# ProPrj_Line_Follower_TURBO_v1_2_2026-04-.net
KiCad netlist of a schematic drawn in EasyEDA Pro
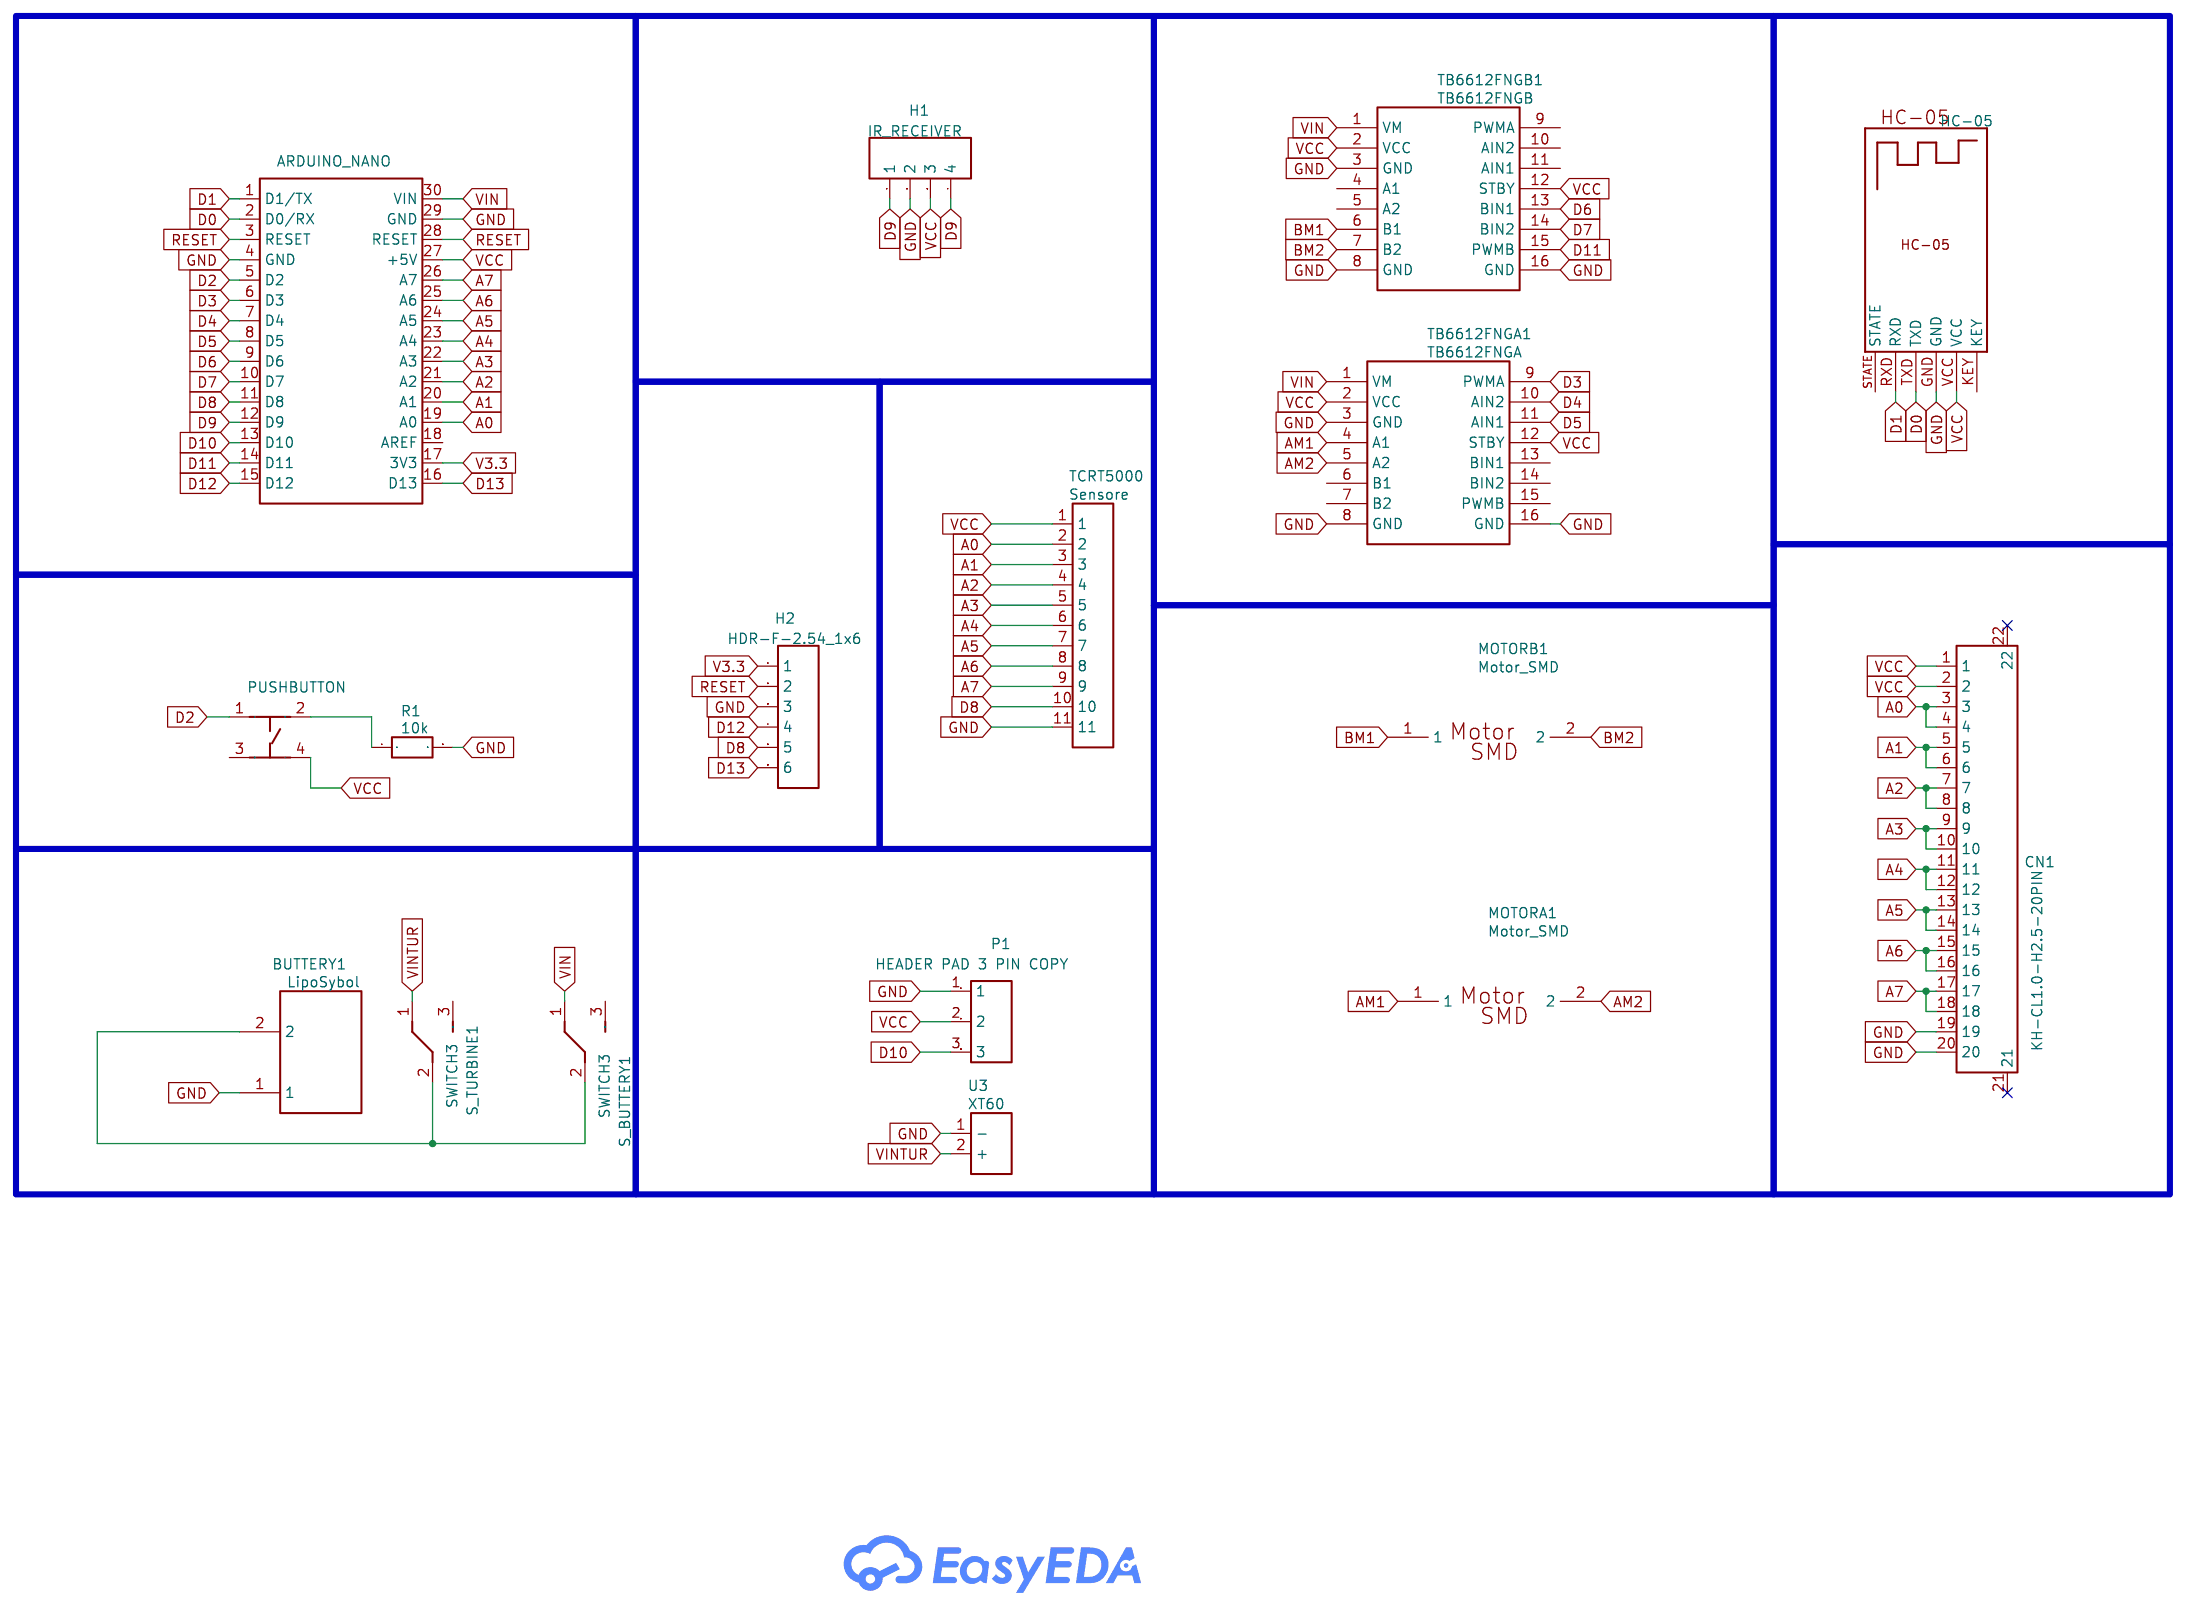
[diagram p0: schematic sheet]

(export (version "E")
  (design (tool "Eeschema 10.0.6"))
  (components
    (comp (ref "1")
      (value "HC-05")
      (footprint "easyedapro:HC-05")
      (fields (field (name "Contributor") "cingoz57"))
      (libsource (lib "easyedapro") (part "HC-05"))
    )
    (comp (ref "ARDUINO_NANO1")
      (value "ARDUINO_NANO")
      (footprint "easyedapro:COMM-TH_ARDUINO_NANO")
      (fields (field (name "Contributor") "lcsc"))
      (libsource (lib "easyedapro") (part "ARDUINO_NANO"))
    )
    (comp (ref "BUTTERY1")
      (value "LipoSybol")
      (footprint "easyedapro:2PIN-RMC")
      (fields (field (name "Contributor") "tech1service"))
      (libsource (lib "easyedapro") (part "LipoSybol"))
    )
    (comp (ref "CN1")
      (value "KH-CL1.0-H2.5-20PIN")
      (footprint "easyedapro:FPC-SMD_KH-CL1.0-H2.5-20PIN")
      (fields (field (name "Manufacturer") "kinghelm(金航标)") (field (name "Contributor") "LCSC"))
      (libsource (lib "easyedapro") (part "KH-CL1.0-H2.5-20PIN"))
    )
    (comp (ref "D2")
      (value "PUSHBUTTON")
      (footprint "easyedapro:SW-SMD_4P-L6.0-W6.0-P4.50-LS10.0_TL3301EF160QG")
      (fields
        (field (name "Manufacturer Part") "4pinTACTPCBTHTPushButton")
        (field (name "Contributor") "LCSC")
      )
      (libsource (lib "easyedapro") (part "PUSHBUTTON"))
    )
    (comp (ref "H1")
      (value "IR_RECEIVER")
      (footprint "easyedapro:HDR-F-2.54_1X4")
      (fields (field (name "Contributor") "LCEDA_Lib"))
      (libsource (lib "easyedapro") (part "IR_RECEIVER"))
    )
    (comp (ref "H2")
      (value "HDR-F-2.54_1x6")
      (footprint "easyedapro:HDR-F-2.54_1X6")
      (fields (field (name "Contributor") "LCEDA_Lib"))
      (libsource (lib "easyedapro") (part "HDR-F-2.54_1x6"))
    )
    (comp (ref "MOTORA1")
      (value "Motor_SMD")
      (footprint "easyedapro:MOTORSMD")
      (fields (field (name "Manufacturer Part") "RayitoCorp") (field (name "Contributor") "Josueking23"))
      (libsource (lib "easyedapro") (part "Motor_SMD"))
    )
    (comp (ref "MOTORB1")
      (value "Motor_SMD")
      (footprint "easyedapro:MOTORSMD")
      (fields (field (name "Manufacturer Part") "RayitoCorp") (field (name "Contributor") "Josueking23"))
      (libsource (lib "easyedapro") (part "Motor_SMD"))
    )
    (comp (ref "P1")
      (value "HEADER PAD 3 PIN COPY")
      (footprint "easyedapro:CONNECTOR_PINHEADER_2.54MM:PINHEADER_1X3")
      (fields
        (field (name "Manufacturer Part") "Female headerHDR1X8-2.54")
        (field (name "Manufacturer") "BOOMELE")
        (field (name "Contributor") "juchani")
      )
      (libsource (lib "easyedapro") (part "HEADER PAD 3 PIN COPY"))
    )
    (comp (ref "R1")
      (value "10k")
      (footprint "easyedapro:R0603")
      (fields (field (name "Contributor") "LCEDA_Lib"))
      (libsource (lib "easyedapro") (part "10k"))
    )
    (comp (ref "S_BUTTERY1")
      (value "SWITCH3")
      (footprint "easyedapro:SWITCH3PINS-DIP")
      (fields (field (name "Contributor") "TruongKhoa"))
      (libsource (lib "easyedapro") (part "SWITCH3"))
    )
    (comp (ref "S_TURBINE1")
      (value "SWITCH3")
      (footprint "easyedapro:SWITCH3PINS-DIP")
      (fields (field (name "Contributor") "TruongKhoa"))
      (libsource (lib "easyedapro") (part "SWITCH3"))
    )
    (comp (ref "TB6612FNGA1")
      (value "TB6612FNGA")
      (footprint "easyedapro:TB6612FNG")
      (fields (field (name "Manufacturer Part") "TB6612FNG") (field (name "Contributor") "NonpawitE"))
      (libsource (lib "easyedapro") (part "TB6612FNGA"))
    )
    (comp (ref "TB6612FNGB1")
      (value "TB6612FNGB")
      (footprint "easyedapro:TB6612FNG")
      (fields (field (name "Manufacturer Part") "TB6612FNG") (field (name "Contributor") "NonpawitE"))
      (libsource (lib "easyedapro") (part "TB6612FNGB"))
    )
    (comp (ref "TCRT5000")
      (value "Sensore")
      (fields (field (name "Manufacturer Part") "HDR-1X11") (field (name "Contributor") "LCSC"))
      (libsource (lib "easyedapro") (part "Sensore"))
    )
    (comp (ref "U3")
      (value "XT60")
      (footprint "easyedapro:CONN-TH_XT60")
      (fields
        (field (name "Manufacturer Part") "XT60-M.")
        (field (name "Manufacturer") "AMASS(艾迈斯)")
        (field (name "Contributor") "lcsc")
      )
      (libsource (lib "easyedapro") (part "XT60"))
    )
  )
  (nets
    (net (code "1") (name "A0") (class "Default")
      (node (ref "ARDUINO_NANO1") (pin "19") (pinfunction "A0_19") (pintype "unspecified"))
      (node (ref "CN1") (pin "3") (pinfunction "3_3") (pintype "unspecified"))
      (node (ref "CN1") (pin "4") (pinfunction "4_4") (pintype "unspecified"))
      (node (ref "TCRT5000") (pin "2") (pinfunction "2_2") (pintype "unspecified"))
    )
    (net (code "2") (name "A1") (class "Default")
      (node (ref "ARDUINO_NANO1") (pin "20") (pinfunction "A1_20") (pintype "unspecified"))
      (node (ref "CN1") (pin "5") (pinfunction "5_5") (pintype "unspecified"))
      (node (ref "CN1") (pin "6") (pinfunction "6_6") (pintype "unspecified"))
      (node (ref "TCRT5000") (pin "3") (pinfunction "3_3") (pintype "unspecified"))
    )
    (net (code "3") (name "A2") (class "Default")
      (node (ref "ARDUINO_NANO1") (pin "21") (pinfunction "A2_21") (pintype "unspecified"))
      (node (ref "CN1") (pin "7") (pinfunction "7_7") (pintype "unspecified"))
      (node (ref "CN1") (pin "8") (pinfunction "8_8") (pintype "unspecified"))
      (node (ref "TCRT5000") (pin "4") (pinfunction "4_4") (pintype "unspecified"))
    )
    (net (code "4") (name "A3") (class "Default")
      (node (ref "ARDUINO_NANO1") (pin "22") (pinfunction "A3_22") (pintype "unspecified"))
      (node (ref "CN1") (pin "10") (pinfunction "10_10") (pintype "unspecified"))
      (node (ref "CN1") (pin "9") (pinfunction "9_9") (pintype "unspecified"))
      (node (ref "TCRT5000") (pin "5") (pinfunction "5_5") (pintype "unspecified"))
    )
    (net (code "5") (name "A4") (class "Default")
      (node (ref "ARDUINO_NANO1") (pin "23") (pinfunction "A4_23") (pintype "unspecified"))
      (node (ref "CN1") (pin "11") (pinfunction "11_11") (pintype "unspecified"))
      (node (ref "CN1") (pin "12") (pinfunction "12_12") (pintype "unspecified"))
      (node (ref "TCRT5000") (pin "6") (pinfunction "6_6") (pintype "unspecified"))
    )
    (net (code "6") (name "A5") (class "Default")
      (node (ref "ARDUINO_NANO1") (pin "24") (pinfunction "A5_24") (pintype "unspecified"))
      (node (ref "CN1") (pin "13") (pinfunction "13_13") (pintype "unspecified"))
      (node (ref "CN1") (pin "14") (pinfunction "14_14") (pintype "unspecified"))
      (node (ref "TCRT5000") (pin "7") (pinfunction "7_7") (pintype "unspecified"))
    )
    (net (code "7") (name "A6") (class "Default")
      (node (ref "ARDUINO_NANO1") (pin "25") (pinfunction "A6_25") (pintype "unspecified"))
      (node (ref "CN1") (pin "15") (pinfunction "15_15") (pintype "unspecified"))
      (node (ref "CN1") (pin "16") (pinfunction "16_16") (pintype "unspecified"))
      (node (ref "TCRT5000") (pin "8") (pinfunction "8_8") (pintype "unspecified"))
    )
    (net (code "8") (name "A7") (class "Default")
      (node (ref "ARDUINO_NANO1") (pin "26") (pinfunction "A7_26") (pintype "unspecified"))
      (node (ref "CN1") (pin "17") (pinfunction "17_17") (pintype "unspecified"))
      (node (ref "CN1") (pin "18") (pinfunction "18_18") (pintype "unspecified"))
      (node (ref "TCRT5000") (pin "9") (pinfunction "9_9") (pintype "unspecified"))
    )
    (net (code "9") (name "AM1") (class "Default")
      (node (ref "MOTORA1") (pin "1") (pinfunction "1_1") (pintype "unspecified"))
      (node (ref "TB6612FNGA1") (pin "4") (pinfunction "A1_4") (pintype "unspecified"))
    )
    (net (code "10") (name "AM2") (class "Default")
      (node (ref "MOTORA1") (pin "2") (pinfunction "2_2") (pintype "unspecified"))
      (node (ref "TB6612FNGA1") (pin "5") (pinfunction "A2_5") (pintype "unspecified"))
    )
    (net (code "11") (name "BM1") (class "Default")
      (node (ref "MOTORB1") (pin "1") (pinfunction "1_1") (pintype "unspecified"))
      (node (ref "TB6612FNGB1") (pin "6") (pinfunction "B1_6") (pintype "unspecified"))
    )
    (net (code "12") (name "BM2") (class "Default")
      (node (ref "MOTORB1") (pin "2") (pinfunction "2_2") (pintype "unspecified"))
      (node (ref "TB6612FNGB1") (pin "7") (pinfunction "B2_7") (pintype "unspecified"))
    )
    (net (code "13") (name "D0") (class "Default")
      (node (ref "1") (pin "TXD") (pinfunction "TXD_TXD") (pintype "bidirectional"))
      (node (ref "ARDUINO_NANO1") (pin "2") (pinfunction "D0/RX_2") (pintype "unspecified"))
    )
    (net (code "14") (name "D1") (class "Default")
      (node (ref "1") (pin "RXD") (pinfunction "RXD_RXD") (pintype "bidirectional"))
      (node (ref "ARDUINO_NANO1") (pin "1") (pinfunction "D1/TX_1") (pintype "unspecified"))
    )
    (net (code "15") (name "D2") (class "Default")
      (node (ref "ARDUINO_NANO1") (pin "5") (pinfunction "D2_5") (pintype "unspecified"))
      (node (ref "D2") (pin "1") (pinfunction "1_1") (pintype "unspecified"))
    )
    (net (code "16") (name "D3") (class "Default")
      (node (ref "ARDUINO_NANO1") (pin "6") (pinfunction "D3_6") (pintype "unspecified"))
      (node (ref "TB6612FNGA1") (pin "9") (pinfunction "PWMA_9") (pintype "unspecified"))
    )
    (net (code "17") (name "D4") (class "Default")
      (node (ref "ARDUINO_NANO1") (pin "7") (pinfunction "D4_7") (pintype "unspecified"))
      (node (ref "TB6612FNGA1") (pin "10") (pinfunction "AIN2_10") (pintype "unspecified"))
    )
    (net (code "18") (name "D5") (class "Default")
      (node (ref "ARDUINO_NANO1") (pin "8") (pinfunction "D5_8") (pintype "unspecified"))
      (node (ref "TB6612FNGA1") (pin "11") (pinfunction "AIN1_11") (pintype "unspecified"))
    )
    (net (code "19") (name "D6") (class "Default")
      (node (ref "ARDUINO_NANO1") (pin "9") (pinfunction "D6_9") (pintype "unspecified"))
      (node (ref "TB6612FNGB1") (pin "13") (pinfunction "BIN1_13") (pintype "unspecified"))
    )
    (net (code "20") (name "D7") (class "Default")
      (node (ref "ARDUINO_NANO1") (pin "10") (pinfunction "D7_10") (pintype "unspecified"))
      (node (ref "TB6612FNGB1") (pin "14") (pinfunction "BIN2_14") (pintype "unspecified"))
    )
    (net (code "21") (name "D8") (class "Default")
      (node (ref "ARDUINO_NANO1") (pin "11") (pinfunction "D8_11") (pintype "unspecified"))
      (node (ref "H2") (pin "5") (pinfunction "5_5") (pintype "input"))
      (node (ref "TCRT5000") (pin "10") (pinfunction "10_10") (pintype "unspecified"))
    )
    (net (code "22") (name "D9") (class "Default")
      (node (ref "ARDUINO_NANO1") (pin "12") (pinfunction "D9_12") (pintype "unspecified"))
      (node (ref "H1") (pin "1") (pinfunction "1_1") (pintype "unspecified"))
      (node (ref "H1") (pin "4") (pinfunction "4_4") (pintype "unspecified"))
    )
    (net (code "23") (name "D10") (class "Default")
      (node (ref "ARDUINO_NANO1") (pin "13") (pinfunction "D10_13") (pintype "unspecified"))
      (node (ref "P1") (pin "3") (pinfunction "3_3") (pintype "unspecified"))
    )
    (net (code "24") (name "D11") (class "Default")
      (node (ref "ARDUINO_NANO1") (pin "14") (pinfunction "D11_14") (pintype "unspecified"))
      (node (ref "TB6612FNGB1") (pin "15") (pinfunction "PWMB_15") (pintype "unspecified"))
    )
    (net (code "25") (name "D12") (class "Default")
      (node (ref "ARDUINO_NANO1") (pin "15") (pinfunction "D12_15") (pintype "unspecified"))
      (node (ref "H2") (pin "4") (pinfunction "4_4") (pintype "input"))
    )
    (net (code "26") (name "D13") (class "Default")
      (node (ref "ARDUINO_NANO1") (pin "16") (pinfunction "D13_16") (pintype "unspecified"))
      (node (ref "H2") (pin "6") (pinfunction "6_6") (pintype "input"))
    )
    (net (code "27") (name "GND") (class "Default")
      (node (ref "1") (pin "GND") (pinfunction "GND_GND") (pintype "bidirectional"))
      (node (ref "ARDUINO_NANO1") (pin "29") (pinfunction "GND_29") (pintype "unspecified"))
      (node (ref "ARDUINO_NANO1") (pin "4") (pinfunction "GND_4") (pintype "unspecified"))
      (node (ref "BUTTERY1") (pin "1") (pinfunction "1_1") (pintype "unspecified"))
      (node (ref "CN1") (pin "19") (pinfunction "19_19") (pintype "unspecified"))
      (node (ref "CN1") (pin "20") (pinfunction "20_20") (pintype "unspecified"))
      (node (ref "H1") (pin "2") (pinfunction "2_2") (pintype "unspecified"))
      (node (ref "H2") (pin "3") (pinfunction "3_3") (pintype "input"))
      (node (ref "P1") (pin "1") (pinfunction "1_1") (pintype "unspecified"))
      (node (ref "R1") (pin "2") (pinfunction "2_2") (pintype "unspecified"))
      (node (ref "TB6612FNGA1") (pin "16") (pinfunction "GND_16") (pintype "unspecified"))
      (node (ref "TB6612FNGA1") (pin "3") (pinfunction "GND_3") (pintype "unspecified"))
      (node (ref "TB6612FNGA1") (pin "8") (pinfunction "GND_8") (pintype "unspecified"))
      (node (ref "TB6612FNGB1") (pin "16") (pinfunction "GND_16") (pintype "unspecified"))
      (node (ref "TB6612FNGB1") (pin "3") (pinfunction "GND_3") (pintype "unspecified"))
      (node (ref "TB6612FNGB1") (pin "8") (pinfunction "GND_8") (pintype "unspecified"))
      (node (ref "TCRT5000") (pin "11") (pinfunction "11_11") (pintype "unspecified"))
      (node (ref "U3") (pin "1") (pinfunction "-_1") (pintype "unspecified"))
    )
    (net (code "28") (name "Net-(BUTTERY1-Pad2)") (class "Default")
      (node (ref "BUTTERY1") (pin "2") (pinfunction "2_2") (pintype "unspecified"))
      (node (ref "S_BUTTERY1") (pin "2") (pintype "unspecified"))
      (node (ref "S_TURBINE1") (pin "2") (pintype "unspecified"))
    )
    (net (code "29") (name "Net-(D2-Pad2)") (class "Default")
      (node (ref "D2") (pin "2") (pinfunction "2_2") (pintype "unspecified"))
      (node (ref "R1") (pin "1") (pinfunction "1_1") (pintype "unspecified"))
    )
    (net (code "30") (name "RESET") (class "Default")
      (node (ref "ARDUINO_NANO1") (pin "28") (pinfunction "RESET_28") (pintype "unspecified"))
      (node (ref "ARDUINO_NANO1") (pin "3") (pinfunction "RESET_3") (pintype "unspecified"))
      (node (ref "H2") (pin "2") (pinfunction "2_2") (pintype "input"))
    )
    (net (code "31") (name "V3.3") (class "Default")
      (node (ref "ARDUINO_NANO1") (pin "17") (pinfunction "3V3_17") (pintype "unspecified"))
      (node (ref "H2") (pin "1") (pinfunction "1_1") (pintype "input"))
    )
    (net (code "32") (name "VCC") (class "Default")
      (node (ref "1") (pin "VCC") (pinfunction "VCC_VCC") (pintype "bidirectional"))
      (node (ref "ARDUINO_NANO1") (pin "27") (pinfunction "+5V_27") (pintype "unspecified"))
      (node (ref "CN1") (pin "1") (pinfunction "1_1") (pintype "unspecified"))
      (node (ref "CN1") (pin "2") (pinfunction "2_2") (pintype "unspecified"))
      (node (ref "D2") (pin "4") (pinfunction "4_4") (pintype "unspecified"))
      (node (ref "H1") (pin "3") (pinfunction "3_3") (pintype "unspecified"))
      (node (ref "P1") (pin "2") (pinfunction "2_2") (pintype "unspecified"))
      (node (ref "TB6612FNGA1") (pin "12") (pinfunction "STBY_12") (pintype "unspecified"))
      (node (ref "TB6612FNGA1") (pin "2") (pinfunction "VCC_2") (pintype "unspecified"))
      (node (ref "TB6612FNGB1") (pin "12") (pinfunction "STBY_12") (pintype "unspecified"))
      (node (ref "TB6612FNGB1") (pin "2") (pinfunction "VCC_2") (pintype "unspecified"))
      (node (ref "TCRT5000") (pin "1") (pinfunction "1_1") (pintype "unspecified"))
    )
    (net (code "33") (name "VIN") (class "Default")
      (node (ref "ARDUINO_NANO1") (pin "30") (pinfunction "VIN_30") (pintype "unspecified"))
      (node (ref "S_BUTTERY1") (pin "1") (pintype "unspecified"))
      (node (ref "TB6612FNGA1") (pin "1") (pinfunction "VM_1") (pintype "unspecified"))
      (node (ref "TB6612FNGB1") (pin "1") (pinfunction "VM_1") (pintype "unspecified"))
    )
    (net (code "34") (name "VINTUR") (class "Default")
      (node (ref "S_TURBINE1") (pin "1") (pintype "unspecified"))
      (node (ref "U3") (pin "2") (pinfunction "+_2") (pintype "unspecified"))
    )
    (net (code "35") (name "unconnected-(1-PadKEY)") (class "Default")
      (node (ref "1") (pin "KEY") (pinfunction "KEY_KEY") (pintype "bidirectional"))
    )
    (net (code "36") (name "unconnected-(1-PadSTATE)") (class "Default")
      (node (ref "1") (pin "STATE") (pinfunction "STATE_STATE") (pintype "bidirectional"))
    )
    (net (code "37") (name "unconnected-(ARDUINO_NANO1-AREF-Pad18)") (class "Default")
      (node (ref "ARDUINO_NANO1") (pin "18") (pinfunction "AREF_18") (pintype "unspecified"))
    )
    (net (code "38") (name "unconnected-(CN1-Pad21)") (class "Default")
      (node (ref "CN1") (pin "21") (pinfunction "21_21") (pintype "unspecified+no_connect"))
    )
    (net (code "39") (name "unconnected-(CN1-Pad22)") (class "Default")
      (node (ref "CN1") (pin "22") (pinfunction "22_22") (pintype "unspecified+no_connect"))
    )
    (net (code "40") (name "unconnected-(D2-Pad3)") (class "Default")
      (node (ref "D2") (pin "3") (pinfunction "3_3") (pintype "unspecified"))
    )
    (net (code "41") (name "unconnected-(S_BUTTERY1-I{slash}O2-Pad3)") (class "Default")
      (node (ref "S_BUTTERY1") (pin "3") (pinfunction "I/O2_3") (pintype "unspecified"))
    )
    (net (code "42") (name "unconnected-(S_TURBINE1-I{slash}O2-Pad3)") (class "Default")
      (node (ref "S_TURBINE1") (pin "3") (pinfunction "I/O2_3") (pintype "unspecified"))
    )
    (net (code "43") (name "unconnected-(TB6612FNGA1-B1-Pad6)") (class "Default")
      (node (ref "TB6612FNGA1") (pin "6") (pinfunction "B1_6") (pintype "unspecified"))
    )
    (net (code "44") (name "unconnected-(TB6612FNGA1-B2-Pad7)") (class "Default")
      (node (ref "TB6612FNGA1") (pin "7") (pinfunction "B2_7") (pintype "unspecified"))
    )
    (net (code "45") (name "unconnected-(TB6612FNGA1-BIN1-Pad13)") (class "Default")
      (node (ref "TB6612FNGA1") (pin "13") (pinfunction "BIN1_13") (pintype "unspecified"))
    )
    (net (code "46") (name "unconnected-(TB6612FNGA1-BIN2-Pad14)") (class "Default")
      (node (ref "TB6612FNGA1") (pin "14") (pinfunction "BIN2_14") (pintype "unspecified"))
    )
    (net (code "47") (name "unconnected-(TB6612FNGA1-PWMB-Pad15)") (class "Default")
      (node (ref "TB6612FNGA1") (pin "15") (pinfunction "PWMB_15") (pintype "unspecified"))
    )
    (net (code "48") (name "unconnected-(TB6612FNGB1-A1-Pad4)") (class "Default")
      (node (ref "TB6612FNGB1") (pin "4") (pinfunction "A1_4") (pintype "unspecified"))
    )
    (net (code "49") (name "unconnected-(TB6612FNGB1-A2-Pad5)") (class "Default")
      (node (ref "TB6612FNGB1") (pin "5") (pinfunction "A2_5") (pintype "unspecified"))
    )
    (net (code "50") (name "unconnected-(TB6612FNGB1-AIN1-Pad11)") (class "Default")
      (node (ref "TB6612FNGB1") (pin "11") (pinfunction "AIN1_11") (pintype "unspecified"))
    )
    (net (code "51") (name "unconnected-(TB6612FNGB1-AIN2-Pad10)") (class "Default")
      (node (ref "TB6612FNGB1") (pin "10") (pinfunction "AIN2_10") (pintype "unspecified"))
    )
    (net (code "52") (name "unconnected-(TB6612FNGB1-PWMA-Pad9)") (class "Default")
      (node (ref "TB6612FNGB1") (pin "9") (pinfunction "PWMA_9") (pintype "unspecified"))
    )
  )
)
